# RFM12B-V1_1.net
KiCad netlist of a schematic drawn in EAGLE
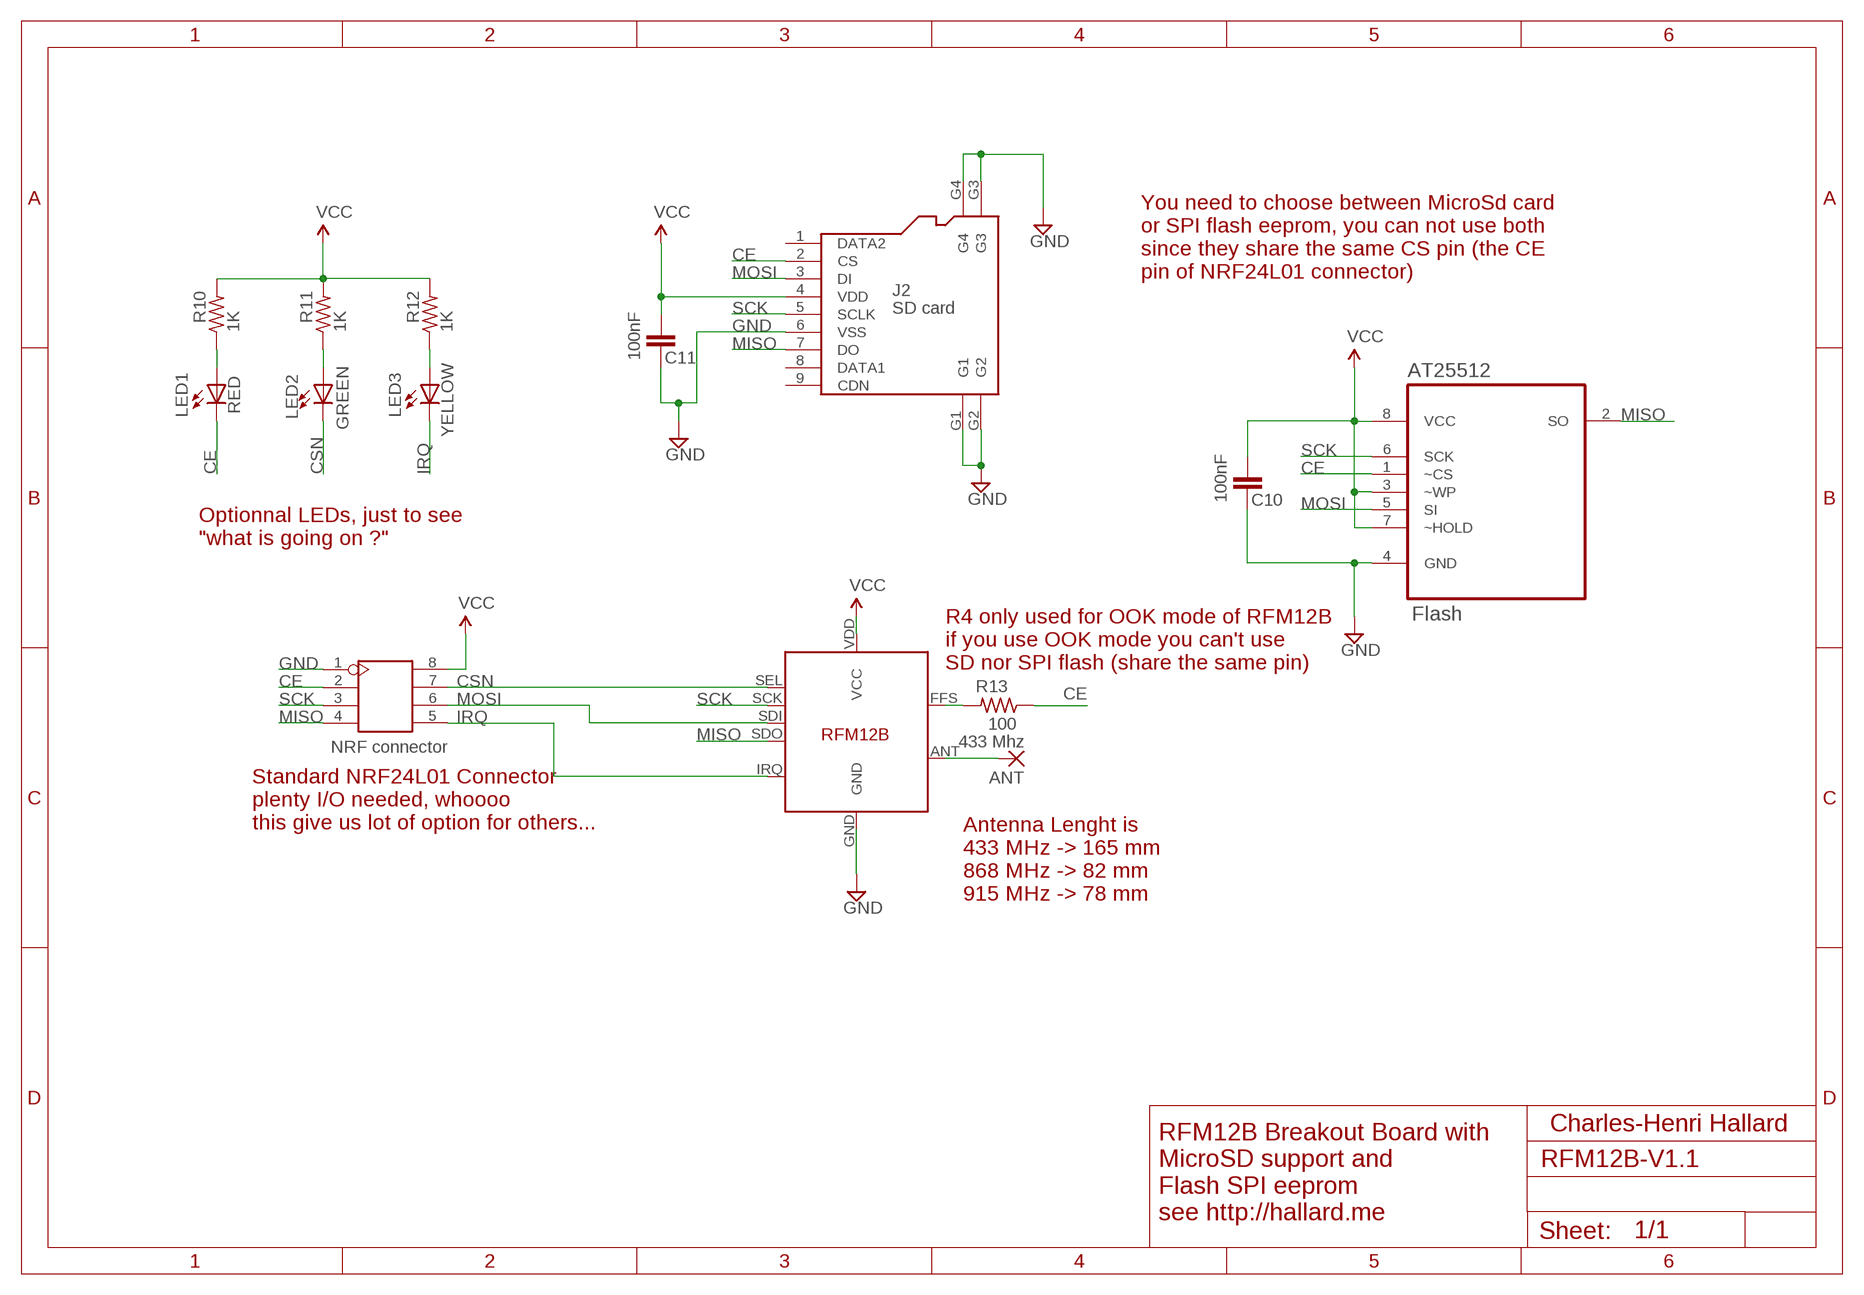
[diagram p0: schematic, sheet 1]

(export (version "E")
  (design (tool "Eeschema 10.0.6"))
  (components
    (comp (ref "ANT")
      (value "433 Mhz")
      (footprint "eagle-import:1,6_0,8")
      (libsource (lib "eagle-import") (part "1,6/0,8"))
    )
    (comp (ref "AT25512")
      (value "Flash")
      (footprint "eagle-import:SOIC127P600X175-8N")
      (fields (field (name "MPN") "AT25512N-SH-B"))
      (libsource (lib "eagle-import") (part "AT25512N-SH-B"))
    )
    (comp (ref "C10")
      (value "100nF")
      (footprint "eagle-import:C0805")
      (libsource (lib "eagle-import") (part "C-EUC0805"))
    )
    (comp (ref "C11")
      (value "100nF")
      (footprint "eagle-import:C0805")
      (libsource (lib "eagle-import") (part "C-EUC0805"))
    )
    (comp (ref "J1")
      (value "NRF connector")
      (footprint "eagle-import:2X4P-2.54")
      (libsource (lib "eagle-import") (part "HEADER-2X4P-2.54"))
    )
    (comp (ref "J2")
      (value "SD card")
      (footprint "eagle-import:9P-SMD-W_-RING")
      (libsource (lib "eagle-import") (part "HOLDER-MICROSD-9P"))
    )
    (comp (ref "LED1")
      (value "RED")
      (footprint "eagle-import:LED-805")
      (libsource (lib "eagle-import") (part "LED-0805"))
    )
    (comp (ref "LED2")
      (value "GREEN")
      (footprint "eagle-import:LED-805")
      (libsource (lib "eagle-import") (part "LED-0805"))
    )
    (comp (ref "LED3")
      (value "YELLOW")
      (footprint "eagle-import:LED-805")
      (libsource (lib "eagle-import") (part "LED-0805"))
    )
    (comp (ref "R10")
      (value "1K")
      (footprint "eagle-import:M0805")
      (libsource (lib "eagle-import") (part "R-US_M0805"))
    )
    (comp (ref "R11")
      (value "1K")
      (footprint "eagle-import:M0805")
      (libsource (lib "eagle-import") (part "R-US_M0805"))
    )
    (comp (ref "R12")
      (value "1K")
      (footprint "eagle-import:M0805")
      (libsource (lib "eagle-import") (part "R-US_M0805"))
    )
    (comp (ref "R13")
      (value "100")
      (footprint "eagle-import:M0805")
      (libsource (lib "eagle-import") (part "R-US_M0805"))
    )
    (comp (ref "U$2")
      (value "RFM12B")
      (footprint "eagle-import:RFM12B")
      (libsource (lib "eagle-import") (part "RFM12B"))
    )
  )
  (nets
    (net (code "1") (name "/CE") (class "Default")
      (node (ref "AT25512") (pin "1") (pinfunction "~{CS}_1") (pintype "input"))
      (node (ref "J1") (pin "2") (pinfunction "2_2") (pintype "bidirectional"))
      (node (ref "J2") (pin "2") (pinfunction "CS_2") (pintype "bidirectional"))
      (node (ref "LED1") (pin "C") (pinfunction "C_C") (pintype "passive"))
      (node (ref "R13") (pin "1") (pinfunction "1_1") (pintype "passive"))
    )
    (net (code "2") (name "/CSN") (class "Default")
      (node (ref "J1") (pin "7") (pinfunction "7_7") (pintype "bidirectional"))
      (node (ref "LED2") (pin "C") (pinfunction "C_C") (pintype "passive"))
      (node (ref "U$2") (pin "SEL") (pinfunction "SEL_SEL") (pintype "input"))
    )
    (net (code "3") (name "/IRQ") (class "Default")
      (node (ref "J1") (pin "5") (pinfunction "5_5") (pintype "bidirectional"))
      (node (ref "LED3") (pin "C") (pinfunction "C_C") (pintype "passive"))
      (node (ref "U$2") (pin "IRQ") (pinfunction "IRQ_IRQ") (pintype "open_collector"))
    )
    (net (code "4") (name "/MISO") (class "Default")
      (node (ref "AT25512") (pin "2") (pinfunction "SO_2") (pintype "output"))
      (node (ref "J1") (pin "4") (pinfunction "4_4") (pintype "bidirectional"))
      (node (ref "J2") (pin "7") (pinfunction "DO_7") (pintype "bidirectional"))
      (node (ref "U$2") (pin "SDO") (pinfunction "SDO_SDO") (pintype "output"))
    )
    (net (code "5") (name "/MOSI") (class "Default")
      (node (ref "AT25512") (pin "5") (pinfunction "SI_5") (pintype "input"))
      (node (ref "J1") (pin "6") (pinfunction "6_6") (pintype "bidirectional"))
      (node (ref "J2") (pin "3") (pinfunction "DI_3") (pintype "bidirectional"))
      (node (ref "U$2") (pin "SDI") (pinfunction "SDI_SDI") (pintype "input"))
    )
    (net (code "6") (name "/SCK") (class "Default")
      (node (ref "AT25512") (pin "6") (pinfunction "SCK_6") (pintype "input"))
      (node (ref "J1") (pin "3") (pinfunction "3_3") (pintype "bidirectional"))
      (node (ref "J2") (pin "5") (pinfunction "SCLK_5") (pintype "bidirectional"))
      (node (ref "U$2") (pin "SCK") (pinfunction "SCK_SCK") (pintype "input"))
    )
    (net (code "7") (name "GND") (class "Default")
      (node (ref "AT25512") (pin "4") (pinfunction "GND_4") (pintype "passive"))
      (node (ref "C10") (pin "2") (pinfunction "2_2") (pintype "passive"))
      (node (ref "C11") (pin "2") (pinfunction "2_2") (pintype "passive"))
      (node (ref "J1") (pin "1") (pinfunction "1_1") (pintype "bidirectional"))
      (node (ref "J2") (pin "6") (pinfunction "VSS_6") (pintype "bidirectional"))
      (node (ref "J2") (pin "G1") (pinfunction "G1_G1") (pintype "bidirectional"))
      (node (ref "J2") (pin "G2") (pinfunction "G2_G2") (pintype "bidirectional"))
      (node (ref "J2") (pin "G3") (pinfunction "G3_G3") (pintype "bidirectional"))
      (node (ref "J2") (pin "G4") (pinfunction "G4_G4") (pintype "bidirectional"))
      (node (ref "U$2") (pin "GND") (pinfunction "GND_GND") (pintype "power_in"))
    )
    (net (code "8") (name "Net-(ANT-P)") (class "Default")
      (node (ref "ANT") (pin "1") (pinfunction "P_1") (pintype "passive"))
      (node (ref "U$2") (pin "ANT") (pinfunction "ANT_ANT") (pintype "passive"))
    )
    (net (code "9") (name "Net-(LED1-PadA)") (class "Default")
      (node (ref "LED1") (pin "A") (pinfunction "A_A") (pintype "passive"))
      (node (ref "R10") (pin "1") (pinfunction "1_1") (pintype "passive"))
    )
    (net (code "10") (name "Net-(LED2-PadA)") (class "Default")
      (node (ref "LED2") (pin "A") (pinfunction "A_A") (pintype "passive"))
      (node (ref "R11") (pin "1") (pinfunction "1_1") (pintype "passive"))
    )
    (net (code "11") (name "Net-(LED3-PadA)") (class "Default")
      (node (ref "LED3") (pin "A") (pinfunction "A_A") (pintype "passive"))
      (node (ref "R12") (pin "1") (pinfunction "1_1") (pintype "passive"))
    )
    (net (code "12") (name "Net-(R13-Pad2)") (class "Default")
      (node (ref "R13") (pin "2") (pinfunction "2_2") (pintype "passive"))
      (node (ref "U$2") (pin "FFS") (pinfunction "FFS_FFS") (pintype "bidirectional"))
    )
    (net (code "13") (name "VCC") (class "Default")
      (node (ref "AT25512") (pin "3") (pinfunction "~{WP}_3") (pintype "input"))
      (node (ref "AT25512") (pin "7") (pinfunction "~{HOLD}_7") (pintype "input"))
      (node (ref "AT25512") (pin "8") (pinfunction "VCC_8") (pintype "power_in"))
      (node (ref "C10") (pin "1") (pinfunction "1_1") (pintype "passive"))
      (node (ref "C11") (pin "1") (pinfunction "1_1") (pintype "passive"))
      (node (ref "J1") (pin "8") (pinfunction "8_8") (pintype "bidirectional"))
      (node (ref "J2") (pin "4") (pinfunction "VDD_4") (pintype "bidirectional"))
      (node (ref "R10") (pin "2") (pinfunction "2_2") (pintype "passive"))
      (node (ref "R11") (pin "2") (pinfunction "2_2") (pintype "passive"))
      (node (ref "R12") (pin "2") (pinfunction "2_2") (pintype "passive"))
      (node (ref "U$2") (pin "VDD") (pinfunction "VCC_VDD") (pintype "power_in"))
    )
    (net (code "14") (name "unconnected-(J2-CDN-Pad9)") (class "Default")
      (node (ref "J2") (pin "9") (pinfunction "CDN_9") (pintype "bidirectional"))
    )
    (net (code "15") (name "unconnected-(J2-DATA1-Pad8)") (class "Default")
      (node (ref "J2") (pin "8") (pinfunction "DATA1_8") (pintype "bidirectional"))
    )
    (net (code "16") (name "unconnected-(J2-DATA2-Pad1)") (class "Default")
      (node (ref "J2") (pin "1") (pinfunction "DATA2_1") (pintype "bidirectional"))
    )
  )
)
